# ESP8266_Amp_THT.net
KiCad netlist of a schematic drawn in Altium Designer
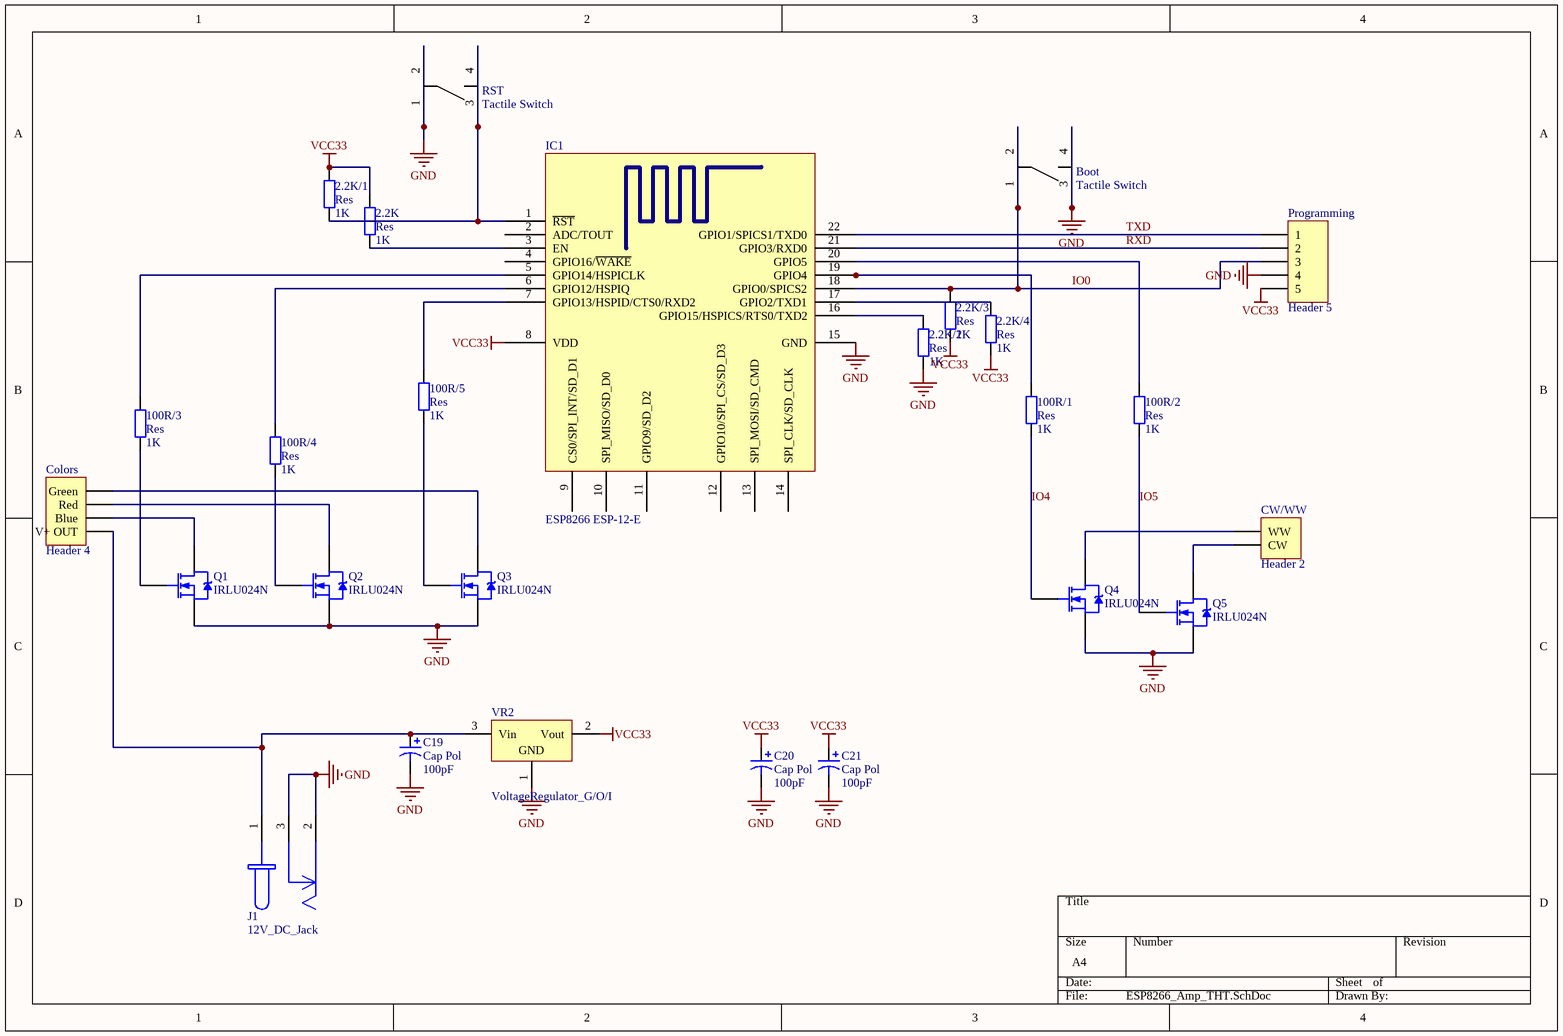
[diagram p0: ESP8266_Amp_THT.SchDoc]

(export (version "E")
  (design (tool "Eeschema 10.0.6"))
  (components
    (comp (ref "2.2K")
      (value "Res")
      (footprint "Res-1/4W")
      (description "Resistor")
      (fields (field (name "ALTIUM_VALUE") "1K") (field (name "PUBLISHER") "Altium Limited"))
      (libsource (lib "cadLib") (part "Res"))
    )
    (comp (ref "2.2K/1")
      (value "Res")
      (footprint "Res-1/4W")
      (description "Resistor")
      (fields (field (name "ALTIUM_VALUE") "1K") (field (name "PUBLISHER") "Altium Limited"))
      (libsource (lib "cadLib") (part "Res"))
    )
    (comp (ref "2.2K/2")
      (value "Res")
      (footprint "Res-1/4W")
      (description "Resistor")
      (fields (field (name "ALTIUM_VALUE") "1K") (field (name "PUBLISHER") "Altium Limited"))
      (libsource (lib "cadLib") (part "Res"))
    )
    (comp (ref "2.2K/3")
      (value "Res")
      (footprint "Res-1/4W")
      (description "Resistor")
      (fields (field (name "ALTIUM_VALUE") "1K") (field (name "PUBLISHER") "Altium Limited"))
      (libsource (lib "cadLib") (part "Res"))
    )
    (comp (ref "2.2K/4")
      (value "Res")
      (footprint "Res-1/4W")
      (description "Resistor")
      (fields (field (name "ALTIUM_VALUE") "1K") (field (name "PUBLISHER") "Altium Limited"))
      (libsource (lib "cadLib") (part "Res"))
    )
    (comp (ref "100R/1")
      (value "Res")
      (footprint "Res-1/4W")
      (description "Resistor")
      (fields (field (name "ALTIUM_VALUE") "1K") (field (name "PUBLISHER") "Altium Limited"))
      (libsource (lib "cadLib") (part "Res"))
    )
    (comp (ref "100R/2")
      (value "Res")
      (footprint "Res-1/4W")
      (description "Resistor")
      (fields (field (name "ALTIUM_VALUE") "1K") (field (name "PUBLISHER") "Altium Limited"))
      (libsource (lib "cadLib") (part "Res"))
    )
    (comp (ref "100R/3")
      (value "Res")
      (footprint "Res-1/4W")
      (description "Resistor")
      (fields (field (name "ALTIUM_VALUE") "1K") (field (name "PUBLISHER") "Altium Limited"))
      (libsource (lib "cadLib") (part "Res"))
    )
    (comp (ref "100R/4")
      (value "Res")
      (footprint "Res-1/4W")
      (description "Resistor")
      (fields (field (name "ALTIUM_VALUE") "1K") (field (name "PUBLISHER") "Altium Limited"))
      (libsource (lib "cadLib") (part "Res"))
    )
    (comp (ref "100R/5")
      (value "Res")
      (footprint "Res-1/4W")
      (description "Resistor")
      (fields (field (name "ALTIUM_VALUE") "1K") (field (name "PUBLISHER") "Altium Limited"))
      (libsource (lib "cadLib") (part "Res"))
    )
    (comp (ref "Boot")
      (value "Tactile Switch")
      (footprint "Tactile-SW")
      (fields (field (name "PUBLISHER") "Altium Limited"))
      (libsource (lib "cadLib") (part "Tact_SW"))
    )
    (comp (ref "C19")
      (value "Cap Pol")
      (footprint "CAPR-2.54mm")
      (description "Polarized Capacitor (Axial)")
      (fields (field (name "ALTIUM_VALUE") "100pF") (field (name "PUBLISHER") "Altium Limited"))
      (libsource (lib "cadLib") (part "Cap Pol"))
    )
    (comp (ref "C20")
      (value "Cap Pol")
      (footprint "CAPR-2.54mm")
      (description "Polarized Capacitor (Axial)")
      (fields (field (name "ALTIUM_VALUE") "100pF") (field (name "PUBLISHER") "Altium Limited"))
      (libsource (lib "cadLib") (part "Cap Pol"))
    )
    (comp (ref "C21")
      (value "Cap Pol")
      (footprint "CAPR-2.54mm")
      (description "Polarized Capacitor (Axial)")
      (fields (field (name "ALTIUM_VALUE") "100pF") (field (name "PUBLISHER") "Altium Limited"))
      (libsource (lib "cadLib") (part "Cap Pol"))
    )
    (comp (ref "Colors")
      (value "Header 4")
      (footprint "HDR1X4")
      (description "Header, 4-Pin")
      (fields (field (name "PUBLISHER") "Altium Limited"))
      (libsource (lib "Miscellaneous Connectors") (part "Header 4"))
    )
    (comp (ref "CW/WW")
      (value "Header 2")
      (footprint "HDR1X2")
      (description "Header, 2-Pin")
      (fields (field (name "PUBLISHER") "Altium Limited"))
      (libsource (lib "Miscellaneous Connectors") (part "Header 2"))
    )
    (comp (ref "IC1")
      (value "ESP8266 ESP-12-E")
      (footprint "ESP8266 ESP-12-E")
      (libsource (lib "cadLib") (part "ESP8266 ESP-12-E"))
    )
    (comp (ref "J1")
      (value "12V_DC_Jack")
      (footprint "694106301002")
      (description "WR-DC DC Power Jack Right Angled(6.4)")
      (fields (field (name "PARTNUMBER") "694106301002") (field (name "PUBLISHER") "Wurth Elektronik"))
      (libsource (lib "cadLib") (part "12V_DC_Jack"))
    )
    (comp (ref "Programming")
      (value "Header 5")
      (footprint "HDR1X5")
      (description "Header, 5-Pin")
      (fields (field (name "PUBLISHER") "Altium Limited"))
      (libsource (lib "Miscellaneous Connectors") (part "Header 5"))
    )
    (comp (ref "Q1")
      (value "IRLU024N")
      (footprint "TO-251AA")
      (description "HEXFET Power MOSFET")
      (fields (field (name "PUBLISHER") "Altium Limited"))
      (libsource (lib "cadLib") (part "IRLU024N"))
    )
    (comp (ref "Q2")
      (value "IRLU024N")
      (footprint "TO-251AA")
      (description "HEXFET Power MOSFET")
      (fields (field (name "PUBLISHER") "Altium Limited"))
      (libsource (lib "cadLib") (part "IRLU024N"))
    )
    (comp (ref "Q3")
      (value "IRLU024N")
      (footprint "TO-251AA")
      (description "HEXFET Power MOSFET")
      (fields (field (name "PUBLISHER") "Altium Limited"))
      (libsource (lib "cadLib") (part "IRLU024N"))
    )
    (comp (ref "Q4")
      (value "IRLU024N")
      (footprint "TO-251AA")
      (description "HEXFET Power MOSFET")
      (fields (field (name "PUBLISHER") "Altium Limited"))
      (libsource (lib "cadLib") (part "IRLU024N"))
    )
    (comp (ref "Q5")
      (value "IRLU024N")
      (footprint "TO-251AA")
      (description "HEXFET Power MOSFET")
      (fields (field (name "PUBLISHER") "Altium Limited"))
      (libsource (lib "cadLib") (part "IRLU024N"))
    )
    (comp (ref "RST")
      (value "Tactile Switch")
      (footprint "Tactile-SW")
      (fields (field (name "PUBLISHER") "Altium Limited"))
      (libsource (lib "cadLib") (part "Tact_SW"))
    )
    (comp (ref "VR2")
      (value "VoltageRegulator_G/O/I")
      (footprint "TO-220AB")
      (description "Voltage Regulator")
      (fields (field (name "PUBLISHER") "Altium Limited"))
      (libsource (lib "cadLib") (part "VoltageRegulator_G/O/I"))
    )
  )
  (nets
    (net (code "1") (name "/IO0") (class "Default")
      (node (ref "2.2K/3") (pin "2") (pinfunction "2_2") (pintype "passive"))
      (node (ref "Boot") (pin "1") (pinfunction "1_1") (pintype "passive"))
      (node (ref "Boot") (pin "2") (pinfunction "2_2") (pintype "passive"))
      (node (ref "IC1") (pin "18") (pinfunction "GPIO0/SPICS2_18") (pintype "passive"))
      (node (ref "Programming") (pin "3") (pinfunction "3_3") (pintype "passive"))
    )
    (net (code "2") (name "/IO4") (class "Default")
      (node (ref "100R/1") (pin "1") (pinfunction "1_1") (pintype "passive"))
      (node (ref "Q4") (pin "1") (pinfunction "G_1") (pintype "passive"))
    )
    (net (code "3") (name "/IO5") (class "Default")
      (node (ref "100R/2") (pin "1") (pinfunction "1_1") (pintype "passive"))
      (node (ref "Q5") (pin "1") (pinfunction "G_1") (pintype "passive"))
    )
    (net (code "4") (name "/RXD") (class "Default")
      (node (ref "IC1") (pin "21") (pinfunction "GPIO3/RXD0_21") (pintype "passive"))
      (node (ref "Programming") (pin "2") (pinfunction "2_2") (pintype "passive"))
    )
    (net (code "5") (name "/TXD") (class "Default")
      (node (ref "IC1") (pin "22") (pinfunction "GPIO1/SPICS1/TXD0_22") (pintype "passive"))
      (node (ref "Programming") (pin "1") (pinfunction "1_1") (pintype "passive"))
    )
    (net (code "6") (name "GND") (class "Default")
      (node (ref "2.2K/2") (pin "1") (pinfunction "1_1") (pintype "passive"))
      (node (ref "Boot") (pin "3") (pinfunction "3_3") (pintype "passive"))
      (node (ref "Boot") (pin "4") (pinfunction "4_4") (pintype "passive"))
      (node (ref "C19") (pin "1") (pinfunction "1_1") (pintype "passive"))
      (node (ref "C20") (pin "1") (pinfunction "1_1") (pintype "passive"))
      (node (ref "C21") (pin "1") (pinfunction "1_1") (pintype "passive"))
      (node (ref "IC1") (pin "15") (pinfunction "GND_15") (pintype "passive"))
      (node (ref "J1") (pin "2") (pinfunction "2_2") (pintype "passive"))
      (node (ref "J1") (pin "3") (pinfunction "3_3") (pintype "passive"))
      (node (ref "Programming") (pin "4") (pinfunction "4_4") (pintype "passive"))
      (node (ref "Q1") (pin "3") (pinfunction "S_3") (pintype "passive"))
      (node (ref "Q2") (pin "3") (pinfunction "S_3") (pintype "passive"))
      (node (ref "Q3") (pin "3") (pinfunction "S_3") (pintype "passive"))
      (node (ref "Q4") (pin "3") (pinfunction "S_3") (pintype "passive"))
      (node (ref "Q5") (pin "3") (pinfunction "S_3") (pintype "passive"))
      (node (ref "RST") (pin "1") (pinfunction "1_1") (pintype "passive"))
      (node (ref "RST") (pin "2") (pinfunction "2_2") (pintype "passive"))
      (node (ref "VR2") (pin "1") (pinfunction "GND_1") (pintype "passive"))
    )
    (net (code "7") (name "Net-(CW/WW-CW)") (class "Default")
      (node (ref "CW/WW") (pin "2") (pinfunction "CW_2") (pintype "passive"))
      (node (ref "Q5") (pin "2") (pinfunction "D_2") (pintype "passive"))
    )
    (net (code "8") (name "Net-(CW/WW-WW)") (class "Default")
      (node (ref "CW/WW") (pin "1") (pinfunction "WW_1") (pintype "passive"))
      (node (ref "Q4") (pin "2") (pinfunction "D_2") (pintype "passive"))
    )
    (net (code "9") (name "Net-(Colors-Blue)") (class "Default")
      (node (ref "Colors") (pin "2") (pinfunction "Blue_2") (pintype "passive"))
      (node (ref "Q1") (pin "2") (pinfunction "D_2") (pintype "passive"))
    )
    (net (code "10") (name "Net-(Colors-Green)") (class "Default")
      (node (ref "Colors") (pin "4") (pinfunction "Green_4") (pintype "passive"))
      (node (ref "Q3") (pin "2") (pinfunction "D_2") (pintype "passive"))
    )
    (net (code "11") (name "Net-(Colors-Red)") (class "Default")
      (node (ref "Colors") (pin "3") (pinfunction "Red_3") (pintype "passive"))
      (node (ref "Q2") (pin "2") (pinfunction "D_2") (pintype "passive"))
    )
    (net (code "12") (name "Net-(Colors-V+_OUT)") (class "Default")
      (node (ref "C19") (pin "2") (pinfunction "2_2") (pintype "passive"))
      (node (ref "Colors") (pin "1") (pinfunction "V+_OUT_1") (pintype "passive"))
      (node (ref "J1") (pin "1") (pinfunction "1_1") (pintype "passive"))
      (node (ref "VR2") (pin "3") (pinfunction "Vin_3") (pintype "passive"))
    )
    (net (code "13") (name "Net-(IC1-EN)") (class "Default")
      (node (ref "2.2K") (pin "1") (pinfunction "1_1") (pintype "passive"))
      (node (ref "IC1") (pin "3") (pinfunction "EN_3") (pintype "passive"))
    )
    (net (code "14") (name "Net-(IC1-GPIO2{slash}TXD1)") (class "Default")
      (node (ref "2.2K/4") (pin "2") (pinfunction "2_2") (pintype "passive"))
      (node (ref "IC1") (pin "17") (pinfunction "GPIO2/TXD1_17") (pintype "passive"))
    )
    (net (code "15") (name "Net-(IC1-GPIO4)") (class "Default")
      (node (ref "100R/1") (pin "2") (pinfunction "2_2") (pintype "passive"))
      (node (ref "IC1") (pin "19") (pinfunction "GPIO4_19") (pintype "passive"))
    )
    (net (code "16") (name "Net-(IC1-GPIO5)") (class "Default")
      (node (ref "100R/2") (pin "2") (pinfunction "2_2") (pintype "passive"))
      (node (ref "IC1") (pin "20") (pinfunction "GPIO5_20") (pintype "passive"))
    )
    (net (code "17") (name "Net-(IC1-GPIO12{slash}HSPIQ)") (class "Default")
      (node (ref "100R/4") (pin "2") (pinfunction "2_2") (pintype "passive"))
      (node (ref "IC1") (pin "6") (pinfunction "GPIO12/HSPIQ_6") (pintype "passive"))
    )
    (net (code "18") (name "Net-(IC1-GPIO13{slash}HSPID{slash}CTS0{slash}RXD2)") (class "Default")
      (node (ref "100R/5") (pin "2") (pinfunction "2_2") (pintype "passive"))
      (node (ref "IC1") (pin "7") (pinfunction "GPIO13/HSPID/CTS0/RXD2_7") (pintype "passive"))
    )
    (net (code "19") (name "Net-(IC1-GPIO14{slash}HSPICLK)") (class "Default")
      (node (ref "100R/3") (pin "2") (pinfunction "2_2") (pintype "passive"))
      (node (ref "IC1") (pin "5") (pinfunction "GPIO14/HSPICLK_5") (pintype "passive"))
    )
    (net (code "20") (name "Net-(IC1-GPIO15{slash}HSPICS{slash}RTS0{slash}TXD2)") (class "Default")
      (node (ref "2.2K/2") (pin "2") (pinfunction "2_2") (pintype "passive"))
      (node (ref "IC1") (pin "16") (pinfunction "GPIO15/HSPICS/RTS0/TXD2_16") (pintype "passive"))
    )
    (net (code "21") (name "Net-(IC1-~{RST})") (class "Default")
      (node (ref "2.2K/1") (pin "1") (pinfunction "1_1") (pintype "passive"))
      (node (ref "IC1") (pin "1") (pinfunction "~{RST}_1") (pintype "passive"))
      (node (ref "RST") (pin "3") (pinfunction "3_3") (pintype "passive"))
      (node (ref "RST") (pin "4") (pinfunction "4_4") (pintype "passive"))
    )
    (net (code "22") (name "Net-(Q1-G)") (class "Default")
      (node (ref "100R/3") (pin "1") (pinfunction "1_1") (pintype "passive"))
      (node (ref "Q1") (pin "1") (pinfunction "G_1") (pintype "passive"))
    )
    (net (code "23") (name "Net-(Q2-G)") (class "Default")
      (node (ref "100R/4") (pin "1") (pinfunction "1_1") (pintype "passive"))
      (node (ref "Q2") (pin "1") (pinfunction "G_1") (pintype "passive"))
    )
    (net (code "24") (name "Net-(Q3-G)") (class "Default")
      (node (ref "100R/5") (pin "1") (pinfunction "1_1") (pintype "passive"))
      (node (ref "Q3") (pin "1") (pinfunction "G_1") (pintype "passive"))
    )
    (net (code "25") (name "VCC33") (class "Default")
      (node (ref "2.2K") (pin "2") (pinfunction "2_2") (pintype "passive"))
      (node (ref "2.2K/1") (pin "2") (pinfunction "2_2") (pintype "passive"))
      (node (ref "2.2K/3") (pin "1") (pinfunction "1_1") (pintype "passive"))
      (node (ref "2.2K/4") (pin "1") (pinfunction "1_1") (pintype "passive"))
      (node (ref "C20") (pin "2") (pinfunction "2_2") (pintype "passive"))
      (node (ref "C21") (pin "2") (pinfunction "2_2") (pintype "passive"))
      (node (ref "IC1") (pin "8") (pinfunction "VDD_8") (pintype "passive"))
      (node (ref "Programming") (pin "5") (pinfunction "5_5") (pintype "passive"))
      (node (ref "VR2") (pin "2") (pinfunction "Vout_2") (pintype "passive"))
    )
    (net (code "26") (name "unconnected-(IC1-ADC{slash}TOUT-Pad2)") (class "Default")
      (node (ref "IC1") (pin "2") (pinfunction "ADC/TOUT_2") (pintype "passive"))
    )
    (net (code "27") (name "unconnected-(IC1-CS0{slash}SPI_INT{slash}SD_D1-Pad9)") (class "Default")
      (node (ref "IC1") (pin "9") (pinfunction "CS0/SPI_INT/SD_D1_9") (pintype "passive"))
    )
    (net (code "28") (name "unconnected-(IC1-GPIO9{slash}SD_D2-Pad11)") (class "Default")
      (node (ref "IC1") (pin "11") (pinfunction "GPIO9/SD_D2_11") (pintype "passive"))
    )
    (net (code "29") (name "unconnected-(IC1-GPIO10{slash}SPI_CS{slash}SD_D3-Pad12)") (class "Default")
      (node (ref "IC1") (pin "12") (pinfunction "GPIO10/SPI_CS/SD_D3_12") (pintype "passive"))
    )
    (net (code "30") (name "unconnected-(IC1-GPIO16{slash}~{WAKE}-Pad4)") (class "Default")
      (node (ref "IC1") (pin "4") (pinfunction "GPIO16/~{WAKE}_4") (pintype "passive"))
    )
    (net (code "31") (name "unconnected-(IC1-SPI_CLK{slash}SD_CLK-Pad14)") (class "Default")
      (node (ref "IC1") (pin "14") (pinfunction "SPI_CLK/SD_CLK_14") (pintype "passive"))
    )
    (net (code "32") (name "unconnected-(IC1-SPI_MISO{slash}SD_D0-Pad10)") (class "Default")
      (node (ref "IC1") (pin "10") (pinfunction "SPI_MISO/SD_D0_10") (pintype "passive"))
    )
    (net (code "33") (name "unconnected-(IC1-SPI_MOSI{slash}SD_CMD-Pad13)") (class "Default")
      (node (ref "IC1") (pin "13") (pinfunction "SPI_MOSI/SD_CMD_13") (pintype "passive"))
    )
  )
)
